# 01_-_Main.net
KiCad netlist of a schematic drawn in Altium Designer
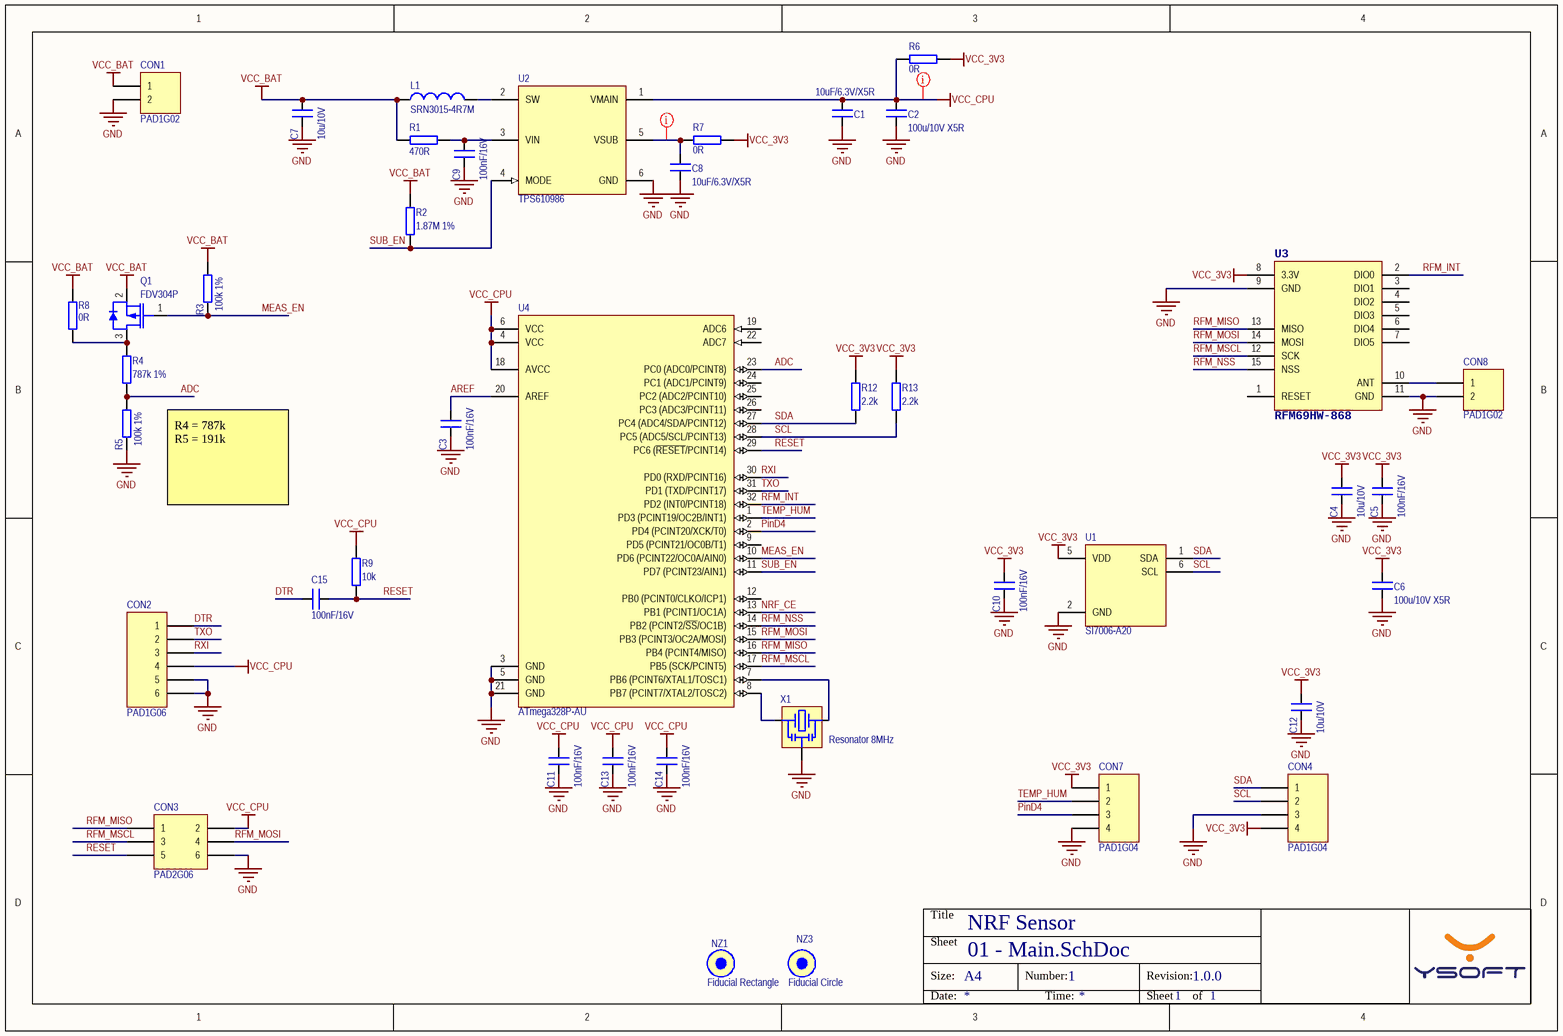
[diagram p0: 01 - Main.SchDoc]

(export (version "E")
  (design (tool "Eeschema 10.0.6"))
  (components
    (comp (ref "C1")
      (value "10uF/6.3V/X5R")
      (footprint "C-0603")
      (description "SMD Ceramic Capacitor 0603 10uF/6.3V/X5R")
      (libsource (lib "Personal Vault") (part "CapacitorNP"))
    )
    (comp (ref "C2")
      (value "100u/10V X5R")
      (footprint "C-1206")
      (description "SMD Ceramic Capacitor 1206 100u/10V X5R")
      (libsource (lib "Personal Vault") (part "CapacitorNP"))
    )
    (comp (ref "C3")
      (value "100nF/16V")
      (footprint "C-0603")
      (description "SMD Ceramic Capacitor 0603 100nF/16V")
      (libsource (lib "Personal Vault") (part "CapacitorNP"))
    )
    (comp (ref "C4")
      (value "10u/10V")
      (footprint "C-0805")
      (description "SMD Ceramic Capacitor 0805 10u/10V")
      (libsource (lib "Personal Vault") (part "CapacitorNP"))
    )
    (comp (ref "C5")
      (value "100nF/16V")
      (footprint "C-0603")
      (description "SMD Ceramic Capacitor 0603 100nF/16V")
      (libsource (lib "Personal Vault") (part "CapacitorNP"))
    )
    (comp (ref "C6")
      (value "100u/10V X5R")
      (footprint "C-1206")
      (description "SMD Ceramic Capacitor 1206 100u/10V X5R")
      (libsource (lib "Personal Vault") (part "CapacitorNP"))
    )
    (comp (ref "C7")
      (value "10u/10V")
      (footprint "C-0805")
      (description "SMD Ceramic Capacitor 0805 10u/10V")
      (libsource (lib "Personal Vault") (part "CapacitorNP"))
    )
    (comp (ref "C8")
      (value "10uF/6.3V/X5R")
      (footprint "C-0603")
      (description "SMD Ceramic Capacitor 0603 10uF/6.3V/X5R")
      (libsource (lib "Personal Vault") (part "CapacitorNP"))
    )
    (comp (ref "C9")
      (value "100nF/16V")
      (footprint "C-0603")
      (description "SMD Ceramic Capacitor 0603 100nF/16V")
      (libsource (lib "Personal Vault") (part "CapacitorNP"))
    )
    (comp (ref "C10")
      (value "100nF/16V")
      (footprint "C-0603")
      (description "SMD Ceramic Capacitor 0603 100nF/16V")
      (libsource (lib "Personal Vault") (part "CapacitorNP"))
    )
    (comp (ref "C11")
      (value "100nF/16V")
      (footprint "C-0603")
      (description "SMD Ceramic Capacitor 0603 100nF/16V")
      (libsource (lib "Personal Vault") (part "CapacitorNP"))
    )
    (comp (ref "C12")
      (value "10u/10V")
      (footprint "C-0805")
      (description "SMD Ceramic Capacitor 0805 10u/10V")
      (libsource (lib "Personal Vault") (part "CapacitorNP"))
    )
    (comp (ref "C13")
      (value "100nF/16V")
      (footprint "C-0603")
      (description "SMD Ceramic Capacitor 0603 100nF/16V")
      (libsource (lib "Personal Vault") (part "CapacitorNP"))
    )
    (comp (ref "C14")
      (value "100nF/16V")
      (footprint "C-0603")
      (description "SMD Ceramic Capacitor 0603 100nF/16V")
      (libsource (lib "Personal Vault") (part "CapacitorNP"))
    )
    (comp (ref "C15")
      (value "100nF/16V")
      (footprint "C-0603")
      (description "SMD Ceramic Capacitor 0603 100nF/16V")
      (libsource (lib "Personal Vault") (part "CapacitorNP"))
    )
    (comp (ref "CON1")
      (value "PAD1G02")
      (footprint "HDR1X02S")
      (description "1x2pin single row pads, 2.54mm")
      (libsource (lib "Personal Vault") (part "Header 2"))
    )
    (comp (ref "CON2")
      (value "PAD1G06")
      (footprint "HDR1X06S")
      (description "1x6pin single row pads, 2.54mm")
      (libsource (lib "Personal Vault") (part "Header 6"))
    )
    (comp (ref "CON3")
      (value "PAD2G06")
      (footprint "HDR2X06S")
      (description "2x3pin dual row pads, 2.54mm")
      (libsource (lib "Personal Vault") (part "Header 3X2"))
    )
    (comp (ref "CON4")
      (value "PAD1G04")
      (footprint "HDR1X04S")
      (description "1x4pin single row pads, 2.54mm")
      (libsource (lib "Personal Vault") (part "Header 4"))
    )
    (comp (ref "CON7")
      (value "PAD1G04")
      (footprint "HDR1X04S")
      (description "1x4pin single row pads, 2.54mm")
      (libsource (lib "Personal Vault") (part "Header 4"))
    )
    (comp (ref "CON8")
      (value "PAD1G02")
      (footprint "HDR1X02S")
      (description "1x2pin single row pads, 2.54mm")
      (fields (field (name "PUBLISHER") "Altium Limited"))
      (libsource (lib "Personal Vault") (part "Header 2"))
    )
    (comp (ref "L1")
      (value "SRN3015-4R7M")
      (footprint "TLU-SRN3015")
      (description "Shielded inductor 4.7uH/1.2A 3x3mm")
      (libsource (lib "Personal Vault") (part "Inductor"))
    )
    (comp (ref "NZ1")
      (value "Fiducial Rectangle")
      (footprint "Fiducial Rectangle")
      (libsource (lib "Personal Vault") (part "Fiducial Mark"))
    )
    (comp (ref "NZ3")
      (value "Fiducial Circle")
      (footprint "Fiducial Circle")
      (libsource (lib "Personal Vault") (part "Fiducial Mark"))
    )
    (comp (ref "Q1")
      (value "FDV304P")
      (footprint "SOT23-3L")
      (description "P-Channel Digital FET 25V, 460mA")
      (libsource (lib "Personal Vault") (part "P-MOSFET"))
    )
    (comp (ref "R1")
      (value "470R")
      (footprint "R-0603")
      (description "SMD Resistor 0603 470R")
      (libsource (lib "Personal Vault") (part "Resistor"))
    )
    (comp (ref "R2")
      (value "1.87M 1%")
      (footprint "R-0603")
      (description "SMD Resistor 0603 1.87M 1%")
      (libsource (lib "Personal Vault") (part "Resistor"))
    )
    (comp (ref "R3")
      (value "100k 1%")
      (footprint "R-0603")
      (description "SMD Resistor 0603 100k 1%")
      (libsource (lib "Personal Vault") (part "Resistor"))
    )
    (comp (ref "R4")
      (value "787k 1%")
      (footprint "R-0603")
      (description "SMD Resistor 0603 787k 1%")
      (libsource (lib "Personal Vault") (part "Resistor"))
    )
    (comp (ref "R5")
      (value "100k 1%")
      (footprint "R-0603")
      (description "SMD Resistor 0603 100k 1%")
      (libsource (lib "Personal Vault") (part "Resistor"))
    )
    (comp (ref "R6")
      (value "0R")
      (footprint "R-0603")
      (description "SMD Resistor 0603 0R")
      (libsource (lib "Personal Vault") (part "Resistor"))
    )
    (comp (ref "R7")
      (value "0R")
      (footprint "R-0603")
      (description "SMD Resistor 0603 0R")
      (libsource (lib "Personal Vault") (part "Resistor"))
    )
    (comp (ref "R8")
      (value "0R")
      (footprint "R-0603")
      (description "SMD Resistor 0603 0R")
      (libsource (lib "Personal Vault") (part "Resistor"))
    )
    (comp (ref "R9")
      (value "10k")
      (footprint "R-0603")
      (description "SMD Resistor 0603 10k")
      (libsource (lib "Personal Vault") (part "Resistor"))
    )
    (comp (ref "R12")
      (value "2.2k")
      (footprint "R-0603")
      (description "SMD Resistor 0603 2k2")
      (libsource (lib "Personal Vault") (part "Resistor"))
    )
    (comp (ref "R13")
      (value "2.2k")
      (footprint "R-0603")
      (description "SMD Resistor 0603 2k2")
      (libsource (lib "Personal Vault") (part "Resistor"))
    )
    (comp (ref "U1")
      (value "SI7006-A20")
      (footprint "DFN100P300X300X60_HS-7N - duplicate")
      (description "I2C Humidity and Temperature Sensor")
      (libsource (lib "Personal Vault") (part "SI7006-A20"))
    )
    (comp (ref "U2")
      (value "TPS610986")
      (footprint "SON50P150X80-6N")
      (description "Ultra-Low Quiescent Current Synchronous Boost with Integrated Load Switch")
      (libsource (lib "Personal Vault") (part "TPS61098x"))
    )
    (comp (ref "U3")
      (value "RFM69HW-868")
      (footprint "RFM69HW-XXXS2")
      (description "RFM69HW ISM TRANSCEIVER MODULE")
      (libsource (lib "Personal Vault") (part "RFM69HW"))
    )
    (comp (ref "U4")
      (value "ATmega328P-AU")
      (footprint "TQFP80P900X900X120-32N")
      (libsource (lib "Arduino") (part "ATmega328P-AU"))
    )
    (comp (ref "X1")
      (value "Resonator 8MHz")
      (footprint "Resonator")
      (libsource (lib "Arduino") (part "Resonator 8MHz"))
    )
  )
  (nets
    (net (code "1") (name "/ADC") (class "Default")
      (node (ref "R4") (pin "1") (pinfunction "1_1") (pintype "passive"))
      (node (ref "R5") (pin "2") (pinfunction "2_2") (pintype "passive"))
      (node (ref "U4") (pin "23") (pinfunction "PC0_(ADC0/PCINT8)_23") (pintype "bidirectional"))
    )
    (net (code "2") (name "/AREF") (class "Default")
      (node (ref "C3") (pin "2") (pinfunction "2_2") (pintype "passive"))
      (node (ref "U4") (pin "20") (pinfunction "AREF_20") (pintype "passive"))
    )
    (net (code "3") (name "/DTR") (class "Default")
      (node (ref "C15") (pin "2") (pinfunction "2_2") (pintype "passive"))
      (node (ref "CON2") (pin "1") (pinfunction "1_1") (pintype "passive"))
    )
    (net (code "4") (name "/MEAS_EN") (class "Default")
      (node (ref "Q1") (pin "1") (pinfunction "GATE_1") (pintype "passive"))
      (node (ref "R3") (pin "1") (pinfunction "1_1") (pintype "passive"))
      (node (ref "U4") (pin "10") (pinfunction "PD6_(PCINT22/OC0A/AIN0)_10") (pintype "bidirectional"))
    )
    (net (code "5") (name "/NRF_CE") (class "Default")
      (node (ref "U4") (pin "13") (pinfunction "PB1_(PCINT1/OC1A)_13") (pintype "bidirectional"))
    )
    (net (code "6") (name "/PinD4") (class "Default")
      (node (ref "CON7") (pin "3") (pinfunction "3_3") (pintype "passive"))
      (node (ref "U4") (pin "2") (pinfunction "PD4_(PCINT20/XCK/T0)_2") (pintype "bidirectional"))
    )
    (net (code "7") (name "/RESET") (class "Default")
      (node (ref "C15") (pin "1") (pinfunction "1_1") (pintype "passive"))
      (node (ref "CON3") (pin "5") (pinfunction "5_5") (pintype "passive"))
      (node (ref "R9") (pin "1") (pinfunction "1_1") (pintype "passive"))
      (node (ref "U4") (pin "29") (pinfunction "PC6_(~{RESET}/PCINT14)_29") (pintype "bidirectional"))
    )
    (net (code "8") (name "/RFM_INT") (class "Default")
      (node (ref "U3") (pin "2") (pinfunction "DIO0_2") (pintype "passive"))
      (node (ref "U4") (pin "32") (pinfunction "PD2_(INT0/PCINT18)_32") (pintype "bidirectional"))
    )
    (net (code "9") (name "/RFM_MISO") (class "Default")
      (node (ref "CON3") (pin "1") (pinfunction "1_1") (pintype "passive"))
      (node (ref "U3") (pin "13") (pinfunction "MISO_13") (pintype "passive"))
      (node (ref "U4") (pin "16") (pinfunction "PB4_(PCINT4/MISO)_16") (pintype "bidirectional"))
    )
    (net (code "10") (name "/RFM_MOSI") (class "Default")
      (node (ref "CON3") (pin "4") (pinfunction "4_4") (pintype "passive"))
      (node (ref "U3") (pin "14") (pinfunction "MOSI_14") (pintype "passive"))
      (node (ref "U4") (pin "15") (pinfunction "PB3_(PCINT3/OC2A/MOSI)_15") (pintype "bidirectional"))
    )
    (net (code "11") (name "/RFM_MSCL") (class "Default")
      (node (ref "CON3") (pin "3") (pinfunction "3_3") (pintype "passive"))
      (node (ref "U3") (pin "12") (pinfunction "SCK_12") (pintype "passive"))
      (node (ref "U4") (pin "17") (pinfunction "PB5_(SCK/PCINT5)_17") (pintype "bidirectional"))
    )
    (net (code "12") (name "/RFM_NSS") (class "Default")
      (node (ref "U3") (pin "15") (pinfunction "NSS_15") (pintype "passive"))
      (node (ref "U4") (pin "14") (pinfunction "PB2_(PCINT2/~{SS}/OC1B)_14") (pintype "bidirectional"))
    )
    (net (code "13") (name "/RXI") (class "Default")
      (node (ref "CON2") (pin "3") (pinfunction "3_3") (pintype "passive"))
      (node (ref "U4") (pin "30") (pinfunction "PD0_(RXD/PCINT16)_30") (pintype "bidirectional"))
    )
    (net (code "14") (name "/SCL") (class "Default")
      (node (ref "CON4") (pin "2") (pinfunction "2_2") (pintype "passive"))
      (node (ref "R13") (pin "1") (pinfunction "1_1") (pintype "passive"))
      (node (ref "U1") (pin "6") (pinfunction "SCL_6") (pintype "passive"))
      (node (ref "U4") (pin "28") (pinfunction "PC5_(ADC5/SCL/PCINT13)_28") (pintype "bidirectional"))
    )
    (net (code "15") (name "/SDA") (class "Default")
      (node (ref "CON4") (pin "1") (pinfunction "1_1") (pintype "passive"))
      (node (ref "R12") (pin "1") (pinfunction "1_1") (pintype "passive"))
      (node (ref "U1") (pin "1") (pinfunction "SDA_1") (pintype "passive"))
      (node (ref "U4") (pin "27") (pinfunction "PC4_(ADC4/SDA/PCINT12)_27") (pintype "bidirectional"))
    )
    (net (code "16") (name "/SUB_EN") (class "Default")
      (node (ref "R2") (pin "1") (pinfunction "1_1") (pintype "passive"))
      (node (ref "U2") (pin "4") (pinfunction "MODE_4") (pintype "input"))
      (node (ref "U4") (pin "11") (pinfunction "PD7_(PCINT23/AIN1)_11") (pintype "bidirectional"))
    )
    (net (code "17") (name "/TEMP_HUM") (class "Default")
      (node (ref "CON7") (pin "2") (pinfunction "2_2") (pintype "passive"))
      (node (ref "U4") (pin "1") (pinfunction "PD3_(PCINT19/OC2B/INT1)_1") (pintype "bidirectional"))
    )
    (net (code "18") (name "/TXO") (class "Default")
      (node (ref "CON2") (pin "2") (pinfunction "2_2") (pintype "passive"))
      (node (ref "U4") (pin "31") (pinfunction "PD1_(TXD/PCINT17)_31") (pintype "bidirectional"))
    )
    (net (code "19") (name "GND") (class "Default")
      (node (ref "C1") (pin "1") (pinfunction "1_1") (pintype "passive"))
      (node (ref "C10") (pin "1") (pinfunction "1_1") (pintype "passive"))
      (node (ref "C11") (pin "1") (pinfunction "1_1") (pintype "passive"))
      (node (ref "C12") (pin "1") (pinfunction "1_1") (pintype "passive"))
      (node (ref "C13") (pin "1") (pinfunction "1_1") (pintype "passive"))
      (node (ref "C14") (pin "1") (pinfunction "1_1") (pintype "passive"))
      (node (ref "C2") (pin "1") (pinfunction "1_1") (pintype "passive"))
      (node (ref "C3") (pin "1") (pinfunction "1_1") (pintype "passive"))
      (node (ref "C4") (pin "1") (pinfunction "1_1") (pintype "passive"))
      (node (ref "C5") (pin "1") (pinfunction "1_1") (pintype "passive"))
      (node (ref "C6") (pin "1") (pinfunction "1_1") (pintype "passive"))
      (node (ref "C7") (pin "1") (pinfunction "1_1") (pintype "passive"))
      (node (ref "C8") (pin "1") (pinfunction "1_1") (pintype "passive"))
      (node (ref "C9") (pin "1") (pinfunction "1_1") (pintype "passive"))
      (node (ref "CON1") (pin "2") (pinfunction "2_2") (pintype "passive"))
      (node (ref "CON2") (pin "5") (pinfunction "5_5") (pintype "passive"))
      (node (ref "CON2") (pin "6") (pinfunction "6_6") (pintype "passive"))
      (node (ref "CON3") (pin "6") (pinfunction "6_6") (pintype "passive"))
      (node (ref "CON4") (pin "3") (pinfunction "3_3") (pintype "passive"))
      (node (ref "CON7") (pin "4") (pinfunction "4_4") (pintype "passive"))
      (node (ref "CON8") (pin "2") (pinfunction "2_2") (pintype "passive"))
      (node (ref "R5") (pin "1") (pinfunction "1_1") (pintype "passive"))
      (node (ref "U1") (pin "2") (pinfunction "GND_2") (pintype "power_in"))
      (node (ref "U2") (pin "6") (pinfunction "GND_6") (pintype "power_in"))
      (node (ref "U3") (pin "11") (pinfunction "GND_11") (pintype "power_in"))
      (node (ref "U3") (pin "9") (pinfunction "GND_9") (pintype "power_in"))
      (node (ref "U4") (pin "21") (pinfunction "GND_21") (pintype "power_in"))
      (node (ref "U4") (pin "3") (pinfunction "GND_3") (pintype "power_in"))
      (node (ref "U4") (pin "5") (pinfunction "GND_5") (pintype "power_in"))
      (node (ref "X1") (pin "2") (pinfunction "GND_2") (pintype "passive"))
    )
    (net (code "20") (name "Net-(Q1-DRAIN)") (class "Default")
      (node (ref "Q1") (pin "3") (pinfunction "DRAIN_3") (pintype "passive"))
      (node (ref "R4") (pin "2") (pinfunction "2_2") (pintype "passive"))
      (node (ref "R8") (pin "1") (pinfunction "1_1") (pintype "passive"))
    )
    (net (code "21") (name "Net-(U2-SW)") (class "Default")
      (node (ref "L1") (pin "2") (pinfunction "2_2") (pintype "passive"))
      (node (ref "U2") (pin "2") (pinfunction "SW_2") (pintype "passive"))
    )
    (net (code "22") (name "Net-(U2-VIN)") (class "Default")
      (node (ref "C9") (pin "2") (pinfunction "2_2") (pintype "passive"))
      (node (ref "R1") (pin "2") (pinfunction "2_2") (pintype "passive"))
      (node (ref "U2") (pin "3") (pinfunction "VIN_3") (pintype "power_in"))
    )
    (net (code "23") (name "Net-(U2-VSUB)") (class "Default")
      (node (ref "C8") (pin "2") (pinfunction "2_2") (pintype "passive"))
      (node (ref "R7") (pin "2") (pinfunction "2_2") (pintype "passive"))
      (node (ref "U2") (pin "5") (pinfunction "VSUB_5") (pintype "passive"))
    )
    (net (code "24") (name "Net-(U3-ANT)") (class "Default")
      (node (ref "CON8") (pin "1") (pinfunction "1_1") (pintype "passive"))
      (node (ref "U3") (pin "10") (pinfunction "ANT_10") (pintype "passive"))
    )
    (net (code "25") (name "Net-(U4-PB6_(PCINT6{slash}XTAL1{slash}TOSC1))") (class "Default")
      (node (ref "U4") (pin "7") (pinfunction "PB6_(PCINT6/XTAL1/TOSC1)_7") (pintype "bidirectional"))
      (node (ref "X1") (pin "3") (pinfunction "X2_3") (pintype "passive"))
    )
    (net (code "26") (name "Net-(U4-PB7_(PCINT7{slash}XTAL2{slash}TOSC2))") (class "Default")
      (node (ref "U4") (pin "8") (pinfunction "PB7_(PCINT7/XTAL2/TOSC2)_8") (pintype "bidirectional"))
      (node (ref "X1") (pin "1") (pinfunction "X1_1") (pintype "passive"))
    )
    (net (code "27") (name "VCC_3V3") (class "Default")
      (node (ref "C10") (pin "2") (pinfunction "2_2") (pintype "passive"))
      (node (ref "C12") (pin "2") (pinfunction "2_2") (pintype "passive"))
      (node (ref "C4") (pin "2") (pinfunction "2_2") (pintype "passive"))
      (node (ref "C5") (pin "2") (pinfunction "2_2") (pintype "passive"))
      (node (ref "C6") (pin "2") (pinfunction "2_2") (pintype "passive"))
      (node (ref "CON4") (pin "4") (pinfunction "4_4") (pintype "passive"))
      (node (ref "CON7") (pin "1") (pinfunction "1_1") (pintype "passive"))
      (node (ref "R12") (pin "2") (pinfunction "2_2") (pintype "passive"))
      (node (ref "R13") (pin "2") (pinfunction "2_2") (pintype "passive"))
      (node (ref "R6") (pin "1") (pinfunction "1_1") (pintype "passive"))
      (node (ref "R7") (pin "1") (pinfunction "1_1") (pintype "passive"))
      (node (ref "U1") (pin "5") (pinfunction "VDD_5") (pintype "power_in"))
      (node (ref "U3") (pin "8") (pinfunction "3.3V_8") (pintype "power_in"))
    )
    (net (code "28") (name "VCC_BAT") (class "Default")
      (node (ref "C7") (pin "2") (pinfunction "2_2") (pintype "passive"))
      (node (ref "CON1") (pin "1") (pinfunction "1_1") (pintype "passive"))
      (node (ref "L1") (pin "1") (pinfunction "1_1") (pintype "passive"))
      (node (ref "Q1") (pin "2") (pinfunction "SOURCE_2") (pintype "passive"))
      (node (ref "R1") (pin "1") (pinfunction "1_1") (pintype "passive"))
      (node (ref "R2") (pin "2") (pinfunction "2_2") (pintype "passive"))
      (node (ref "R3") (pin "2") (pinfunction "2_2") (pintype "passive"))
      (node (ref "R8") (pin "2") (pinfunction "2_2") (pintype "passive"))
    )
    (net (code "29") (name "VCC_CPU") (class "Default")
      (node (ref "C1") (pin "2") (pinfunction "2_2") (pintype "passive"))
      (node (ref "C11") (pin "2") (pinfunction "2_2") (pintype "passive"))
      (node (ref "C13") (pin "2") (pinfunction "2_2") (pintype "passive"))
      (node (ref "C14") (pin "2") (pinfunction "2_2") (pintype "passive"))
      (node (ref "C2") (pin "2") (pinfunction "2_2") (pintype "passive"))
      (node (ref "CON2") (pin "4") (pinfunction "4_4") (pintype "passive"))
      (node (ref "CON3") (pin "2") (pinfunction "2_2") (pintype "passive"))
      (node (ref "R6") (pin "2") (pinfunction "2_2") (pintype "passive"))
      (node (ref "R9") (pin "2") (pinfunction "2_2") (pintype "passive"))
      (node (ref "U2") (pin "1") (pinfunction "VMAIN_1") (pintype "passive"))
      (node (ref "U4") (pin "18") (pinfunction "AVCC_18") (pintype "power_in"))
      (node (ref "U4") (pin "4") (pinfunction "VCC_4") (pintype "power_in"))
      (node (ref "U4") (pin "6") (pinfunction "VCC_6") (pintype "power_in"))
    )
    (net (code "30") (name "unconnected-(U3-DIO1-Pad3)") (class "Default")
      (node (ref "U3") (pin "3") (pinfunction "DIO1_3") (pintype "passive"))
    )
    (net (code "31") (name "unconnected-(U3-DIO2-Pad4)") (class "Default")
      (node (ref "U3") (pin "4") (pinfunction "DIO2_4") (pintype "passive"))
    )
    (net (code "32") (name "unconnected-(U3-DIO3-Pad5)") (class "Default")
      (node (ref "U3") (pin "5") (pinfunction "DIO3_5") (pintype "passive"))
    )
    (net (code "33") (name "unconnected-(U3-DIO4-Pad6)") (class "Default")
      (node (ref "U3") (pin "6") (pinfunction "DIO4_6") (pintype "passive"))
    )
    (net (code "34") (name "unconnected-(U3-DIO5-Pad7)") (class "Default")
      (node (ref "U3") (pin "7") (pinfunction "DIO5_7") (pintype "passive"))
    )
    (net (code "35") (name "unconnected-(U3-RESET-Pad1)") (class "Default")
      (node (ref "U3") (pin "1") (pinfunction "RESET_1") (pintype "passive"))
    )
    (net (code "36") (name "unconnected-(U4-ADC6-Pad19)") (class "Default")
      (node (ref "U4") (pin "19") (pinfunction "ADC6_19") (pintype "input"))
    )
    (net (code "37") (name "unconnected-(U4-ADC7-Pad22)") (class "Default")
      (node (ref "U4") (pin "22") (pinfunction "ADC7_22") (pintype "input"))
    )
    (net (code "38") (name "unconnected-(U4-PB0_(PCINT0{slash}CLKO{slash}ICP1)-Pad12)") (class "Default")
      (node (ref "U4") (pin "12") (pinfunction "PB0_(PCINT0/CLKO/ICP1)_12") (pintype "bidirectional"))
    )
    (net (code "39") (name "unconnected-(U4-PC1_(ADC1{slash}PCINT9)-Pad24)") (class "Default")
      (node (ref "U4") (pin "24") (pinfunction "PC1_(ADC1/PCINT9)_24") (pintype "bidirectional"))
    )
    (net (code "40") (name "unconnected-(U4-PC2_(ADC2{slash}PCINT10)-Pad25)") (class "Default")
      (node (ref "U4") (pin "25") (pinfunction "PC2_(ADC2/PCINT10)_25") (pintype "bidirectional"))
    )
    (net (code "41") (name "unconnected-(U4-PC3_(ADC3{slash}PCINT11)-Pad26)") (class "Default")
      (node (ref "U4") (pin "26") (pinfunction "PC3_(ADC3/PCINT11)_26") (pintype "bidirectional"))
    )
    (net (code "42") (name "unconnected-(U4-PD5_(PCINT21{slash}OC0B{slash}T1)-Pad9)") (class "Default")
      (node (ref "U4") (pin "9") (pinfunction "PD5_(PCINT21/OC0B/T1)_9") (pintype "bidirectional"))
    )
  )
)
